# DME_Board_1.net
KiCad netlist of a schematic drawn in EAGLE
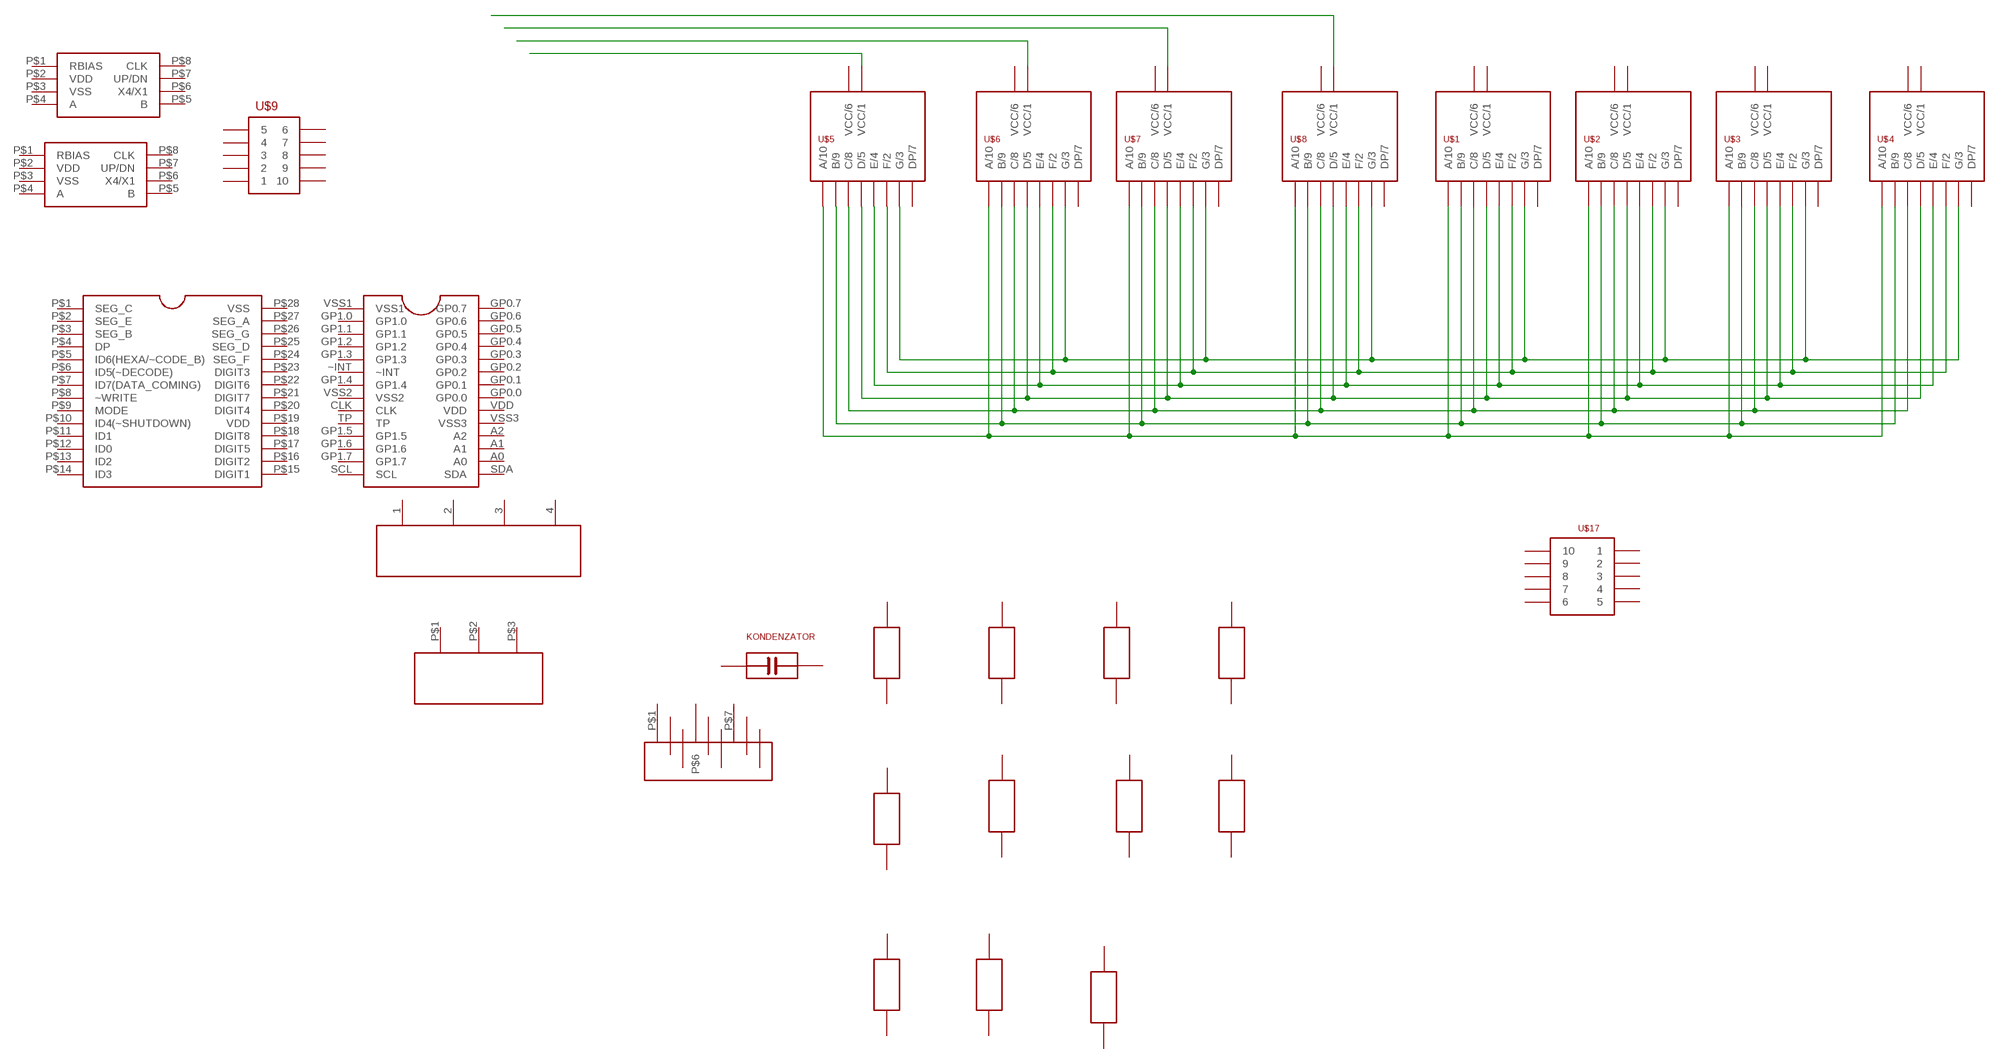
[diagram p0: schematic, sheet 1]

(export (version "E")
  (design (tool "Eeschema 10.0.6"))
  (components
    (comp (ref "U$1")
      (value "SA3611EWA")
      (footprint "eagle-import:SA3611EWA")
      (libsource (lib "eagle-import") (part "SA3611EWA"))
    )
    (comp (ref "U$2")
      (value "SA3611EWA")
      (footprint "eagle-import:SA3611EWA")
      (libsource (lib "eagle-import") (part "SA3611EWA"))
    )
    (comp (ref "U$3")
      (value "SA3611EWA")
      (footprint "eagle-import:SA3611EWA")
      (libsource (lib "eagle-import") (part "SA3611EWA"))
    )
    (comp (ref "U$4")
      (value "SA3611EWA")
      (footprint "eagle-import:SA3611EWA")
      (libsource (lib "eagle-import") (part "SA3611EWA"))
    )
    (comp (ref "U$5")
      (value "SA3611EWA")
      (footprint "eagle-import:SA3611EWA")
      (libsource (lib "eagle-import") (part "SA3611EWA"))
    )
    (comp (ref "U$6")
      (value "SA3611EWA")
      (footprint "eagle-import:SA3611EWA")
      (libsource (lib "eagle-import") (part "SA3611EWA"))
    )
    (comp (ref "U$7")
      (value "SA3611EWA")
      (footprint "eagle-import:SA3611EWA")
      (libsource (lib "eagle-import") (part "SA3611EWA"))
    )
    (comp (ref "U$8")
      (value "SA3611EWA")
      (footprint "eagle-import:SA3611EWA")
      (libsource (lib "eagle-import") (part "SA3611EWA"))
    )
    (comp (ref "U$9")
      (value "ELMA_E37")
      (footprint "eagle-import:ELMA_E37")
      (libsource (lib "eagle-import") (part "ELMA_E37"))
    )
    (comp (ref "U$10")
      (value "46311LD")
      (footprint "eagle-import:46311LD")
      (libsource (lib "eagle-import") (part "46311LD"))
    )
    (comp (ref "U$11")
      (value "REZISTOR")
      (footprint "eagle-import:REZISTOR")
      (libsource (lib "eagle-import") (part "REZISTOR"))
    )
    (comp (ref "U$12")
      (value "T220")
      (footprint "eagle-import:T220")
      (libsource (lib "eagle-import") (part "T220"))
    )
    (comp (ref "U$13")
      (value "REZISTOR")
      (footprint "eagle-import:REZISTOR")
      (libsource (lib "eagle-import") (part "REZISTOR"))
    )
    (comp (ref "U$14")
      (value "ICM7228A")
      (footprint "eagle-import:ICM7228A")
      (libsource (lib "eagle-import") (part "ICM7228A"))
    )
    (comp (ref "U$15")
      (value "REZISTOR")
      (footprint "eagle-import:REZISTOR")
      (libsource (lib "eagle-import") (part "REZISTOR"))
    )
    (comp (ref "U$16")
      (value "MCP23016")
      (footprint "eagle-import:MCP23016")
      (libsource (lib "eagle-import") (part "MCP23016"))
    )
    (comp (ref "U$17")
      (value "LISTA_2X5")
      (footprint "eagle-import:LISTA_2X5")
      (libsource (lib "eagle-import") (part "LISTA_2X5"))
    )
    (comp (ref "U$19")
      (value "REZISTOR")
      (footprint "eagle-import:REZISTOR")
      (libsource (lib "eagle-import") (part "REZISTOR"))
    )
    (comp (ref "U$21")
      (value "LS7084")
      (footprint "eagle-import:LS7084")
      (libsource (lib "eagle-import") (part "LS7084"))
    )
    (comp (ref "U$22")
      (value "LS7084")
      (footprint "eagle-import:LS7084")
      (libsource (lib "eagle-import") (part "LS7084"))
    )
    (comp (ref "U$23")
      (value "KONDENZATOR")
      (footprint "eagle-import:KONDENZATOR")
      (libsource (lib "eagle-import") (part "KONDENZATOR"))
    )
    (comp (ref "U$24")
      (value "ADRESA_0..2")
      (footprint "eagle-import:ADRESA_0..2")
      (libsource (lib "eagle-import") (part "ADRESA_0..2"))
    )
    (comp (ref "U$25")
      (value "REZISTOR")
      (footprint "eagle-import:REZISTOR")
      (libsource (lib "eagle-import") (part "REZISTOR"))
    )
    (comp (ref "U$26")
      (value "REZISTOR")
      (footprint "eagle-import:REZISTOR")
      (libsource (lib "eagle-import") (part "REZISTOR"))
    )
    (comp (ref "U$27")
      (value "REZISTOR")
      (footprint "eagle-import:REZISTOR")
      (libsource (lib "eagle-import") (part "REZISTOR"))
    )
    (comp (ref "U$28")
      (value "REZISTOR")
      (footprint "eagle-import:REZISTOR")
      (libsource (lib "eagle-import") (part "REZISTOR"))
    )
    (comp (ref "U$29")
      (value "REZISTOR")
      (footprint "eagle-import:REZISTOR")
      (libsource (lib "eagle-import") (part "REZISTOR"))
    )
    (comp (ref "U$30")
      (value "REZISTOR")
      (footprint "eagle-import:REZISTOR")
      (libsource (lib "eagle-import") (part "REZISTOR"))
    )
    (comp (ref "U$31")
      (value "REZISTOR")
      (footprint "eagle-import:REZISTOR")
      (libsource (lib "eagle-import") (part "REZISTOR"))
    )
  )
  (nets
    (net (code "1") (name "Net-(U$1-A{slash}10)") (class "Default")
      (node (ref "U$1") (pin "10") (pinfunction "A/10_10") (pintype "bidirectional"))
      (node (ref "U$2") (pin "10") (pinfunction "A/10_10") (pintype "bidirectional"))
      (node (ref "U$3") (pin "10") (pinfunction "A/10_10") (pintype "bidirectional"))
      (node (ref "U$4") (pin "10") (pinfunction "A/10_10") (pintype "bidirectional"))
      (node (ref "U$5") (pin "10") (pinfunction "A/10_10") (pintype "bidirectional"))
      (node (ref "U$6") (pin "10") (pinfunction "A/10_10") (pintype "bidirectional"))
      (node (ref "U$7") (pin "10") (pinfunction "A/10_10") (pintype "bidirectional"))
      (node (ref "U$8") (pin "10") (pinfunction "A/10_10") (pintype "bidirectional"))
    )
    (net (code "2") (name "Net-(U$1-B{slash}9)") (class "Default")
      (node (ref "U$1") (pin "9") (pinfunction "B/9_9") (pintype "bidirectional"))
      (node (ref "U$2") (pin "9") (pinfunction "B/9_9") (pintype "bidirectional"))
      (node (ref "U$3") (pin "9") (pinfunction "B/9_9") (pintype "bidirectional"))
      (node (ref "U$4") (pin "9") (pinfunction "B/9_9") (pintype "bidirectional"))
      (node (ref "U$5") (pin "9") (pinfunction "B/9_9") (pintype "bidirectional"))
      (node (ref "U$6") (pin "9") (pinfunction "B/9_9") (pintype "bidirectional"))
      (node (ref "U$7") (pin "9") (pinfunction "B/9_9") (pintype "bidirectional"))
      (node (ref "U$8") (pin "9") (pinfunction "B/9_9") (pintype "bidirectional"))
    )
    (net (code "3") (name "Net-(U$1-C{slash}8)") (class "Default")
      (node (ref "U$1") (pin "8") (pinfunction "C/8_8") (pintype "bidirectional"))
      (node (ref "U$2") (pin "8") (pinfunction "C/8_8") (pintype "bidirectional"))
      (node (ref "U$3") (pin "8") (pinfunction "C/8_8") (pintype "bidirectional"))
      (node (ref "U$4") (pin "8") (pinfunction "C/8_8") (pintype "bidirectional"))
      (node (ref "U$5") (pin "8") (pinfunction "C/8_8") (pintype "bidirectional"))
      (node (ref "U$6") (pin "8") (pinfunction "C/8_8") (pintype "bidirectional"))
      (node (ref "U$7") (pin "8") (pinfunction "C/8_8") (pintype "bidirectional"))
      (node (ref "U$8") (pin "8") (pinfunction "C/8_8") (pintype "bidirectional"))
    )
    (net (code "4") (name "Net-(U$1-D{slash}5)") (class "Default")
      (node (ref "U$1") (pin "5") (pinfunction "D/5_5") (pintype "bidirectional"))
      (node (ref "U$2") (pin "5") (pinfunction "D/5_5") (pintype "bidirectional"))
      (node (ref "U$3") (pin "5") (pinfunction "D/5_5") (pintype "bidirectional"))
      (node (ref "U$4") (pin "5") (pinfunction "D/5_5") (pintype "bidirectional"))
      (node (ref "U$5") (pin "5") (pinfunction "D/5_5") (pintype "bidirectional"))
      (node (ref "U$6") (pin "5") (pinfunction "D/5_5") (pintype "bidirectional"))
      (node (ref "U$7") (pin "5") (pinfunction "D/5_5") (pintype "bidirectional"))
      (node (ref "U$8") (pin "5") (pinfunction "D/5_5") (pintype "bidirectional"))
    )
    (net (code "5") (name "Net-(U$1-E{slash}4)") (class "Default")
      (node (ref "U$1") (pin "4") (pinfunction "E/4_4") (pintype "bidirectional"))
      (node (ref "U$2") (pin "4") (pinfunction "E/4_4") (pintype "bidirectional"))
      (node (ref "U$3") (pin "4") (pinfunction "E/4_4") (pintype "bidirectional"))
      (node (ref "U$4") (pin "4") (pinfunction "E/4_4") (pintype "bidirectional"))
      (node (ref "U$5") (pin "4") (pinfunction "E/4_4") (pintype "bidirectional"))
      (node (ref "U$6") (pin "4") (pinfunction "E/4_4") (pintype "bidirectional"))
      (node (ref "U$7") (pin "4") (pinfunction "E/4_4") (pintype "bidirectional"))
      (node (ref "U$8") (pin "4") (pinfunction "E/4_4") (pintype "bidirectional"))
    )
    (net (code "6") (name "Net-(U$1-F{slash}2)") (class "Default")
      (node (ref "U$1") (pin "2") (pinfunction "F/2_2") (pintype "bidirectional"))
      (node (ref "U$2") (pin "2") (pinfunction "F/2_2") (pintype "bidirectional"))
      (node (ref "U$3") (pin "2") (pinfunction "F/2_2") (pintype "bidirectional"))
      (node (ref "U$4") (pin "2") (pinfunction "F/2_2") (pintype "bidirectional"))
      (node (ref "U$5") (pin "2") (pinfunction "F/2_2") (pintype "bidirectional"))
      (node (ref "U$6") (pin "2") (pinfunction "F/2_2") (pintype "bidirectional"))
      (node (ref "U$7") (pin "2") (pinfunction "F/2_2") (pintype "bidirectional"))
      (node (ref "U$8") (pin "2") (pinfunction "F/2_2") (pintype "bidirectional"))
    )
    (net (code "7") (name "Net-(U$1-G{slash}3)") (class "Default")
      (node (ref "U$1") (pin "3") (pinfunction "G/3_3") (pintype "bidirectional"))
      (node (ref "U$2") (pin "3") (pinfunction "G/3_3") (pintype "bidirectional"))
      (node (ref "U$3") (pin "3") (pinfunction "G/3_3") (pintype "bidirectional"))
      (node (ref "U$4") (pin "3") (pinfunction "G/3_3") (pintype "bidirectional"))
      (node (ref "U$5") (pin "3") (pinfunction "G/3_3") (pintype "bidirectional"))
      (node (ref "U$6") (pin "3") (pinfunction "G/3_3") (pintype "bidirectional"))
      (node (ref "U$7") (pin "3") (pinfunction "G/3_3") (pintype "bidirectional"))
      (node (ref "U$8") (pin "3") (pinfunction "G/3_3") (pintype "bidirectional"))
    )
    (net (code "8") (name "unconnected-(U$1-DP{slash}7-Pad7)") (class "Default")
      (node (ref "U$1") (pin "7") (pinfunction "DP/7_7") (pintype "bidirectional"))
    )
    (net (code "9") (name "unconnected-(U$1-VCC{slash}1-Pad1)") (class "Default")
      (node (ref "U$1") (pin "1") (pinfunction "VCC/1_1") (pintype "bidirectional"))
    )
    (net (code "10") (name "unconnected-(U$1-VCC{slash}6-Pad6)") (class "Default")
      (node (ref "U$1") (pin "6") (pinfunction "VCC/6_6") (pintype "bidirectional"))
    )
    (net (code "11") (name "unconnected-(U$2-DP{slash}7-Pad7)") (class "Default")
      (node (ref "U$2") (pin "7") (pinfunction "DP/7_7") (pintype "bidirectional"))
    )
    (net (code "12") (name "unconnected-(U$2-VCC{slash}1-Pad1)") (class "Default")
      (node (ref "U$2") (pin "1") (pinfunction "VCC/1_1") (pintype "bidirectional"))
    )
    (net (code "13") (name "unconnected-(U$2-VCC{slash}6-Pad6)") (class "Default")
      (node (ref "U$2") (pin "6") (pinfunction "VCC/6_6") (pintype "bidirectional"))
    )
    (net (code "14") (name "unconnected-(U$3-DP{slash}7-Pad7)") (class "Default")
      (node (ref "U$3") (pin "7") (pinfunction "DP/7_7") (pintype "bidirectional"))
    )
    (net (code "15") (name "unconnected-(U$3-VCC{slash}1-Pad1)") (class "Default")
      (node (ref "U$3") (pin "1") (pinfunction "VCC/1_1") (pintype "bidirectional"))
    )
    (net (code "16") (name "unconnected-(U$3-VCC{slash}6-Pad6)") (class "Default")
      (node (ref "U$3") (pin "6") (pinfunction "VCC/6_6") (pintype "bidirectional"))
    )
    (net (code "17") (name "unconnected-(U$4-DP{slash}7-Pad7)") (class "Default")
      (node (ref "U$4") (pin "7") (pinfunction "DP/7_7") (pintype "bidirectional"))
    )
    (net (code "18") (name "unconnected-(U$4-VCC{slash}1-Pad1)") (class "Default")
      (node (ref "U$4") (pin "1") (pinfunction "VCC/1_1") (pintype "bidirectional"))
    )
    (net (code "19") (name "unconnected-(U$4-VCC{slash}6-Pad6)") (class "Default")
      (node (ref "U$4") (pin "6") (pinfunction "VCC/6_6") (pintype "bidirectional"))
    )
    (net (code "20") (name "unconnected-(U$5-DP{slash}7-Pad7)") (class "Default")
      (node (ref "U$5") (pin "7") (pinfunction "DP/7_7") (pintype "bidirectional"))
    )
    (net (code "21") (name "unconnected-(U$5-VCC{slash}1-Pad1)") (class "Default")
      (node (ref "U$5") (pin "1") (pinfunction "VCC/1_1") (pintype "bidirectional"))
    )
    (net (code "22") (name "unconnected-(U$5-VCC{slash}6-Pad6)") (class "Default")
      (node (ref "U$5") (pin "6") (pinfunction "VCC/6_6") (pintype "bidirectional"))
    )
    (net (code "23") (name "unconnected-(U$6-DP{slash}7-Pad7)") (class "Default")
      (node (ref "U$6") (pin "7") (pinfunction "DP/7_7") (pintype "bidirectional"))
    )
    (net (code "24") (name "unconnected-(U$6-VCC{slash}1-Pad1)") (class "Default")
      (node (ref "U$6") (pin "1") (pinfunction "VCC/1_1") (pintype "bidirectional"))
    )
    (net (code "25") (name "unconnected-(U$6-VCC{slash}6-Pad6)") (class "Default")
      (node (ref "U$6") (pin "6") (pinfunction "VCC/6_6") (pintype "bidirectional"))
    )
    (net (code "26") (name "unconnected-(U$7-DP{slash}7-Pad7)") (class "Default")
      (node (ref "U$7") (pin "7") (pinfunction "DP/7_7") (pintype "bidirectional"))
    )
    (net (code "27") (name "unconnected-(U$7-VCC{slash}1-Pad1)") (class "Default")
      (node (ref "U$7") (pin "1") (pinfunction "VCC/1_1") (pintype "bidirectional"))
    )
    (net (code "28") (name "unconnected-(U$7-VCC{slash}6-Pad6)") (class "Default")
      (node (ref "U$7") (pin "6") (pinfunction "VCC/6_6") (pintype "bidirectional"))
    )
    (net (code "29") (name "unconnected-(U$8-DP{slash}7-Pad7)") (class "Default")
      (node (ref "U$8") (pin "7") (pinfunction "DP/7_7") (pintype "bidirectional"))
    )
    (net (code "30") (name "unconnected-(U$8-VCC{slash}1-Pad1)") (class "Default")
      (node (ref "U$8") (pin "1") (pinfunction "VCC/1_1") (pintype "bidirectional"))
    )
    (net (code "31") (name "unconnected-(U$8-VCC{slash}6-Pad6)") (class "Default")
      (node (ref "U$8") (pin "6") (pinfunction "VCC/6_6") (pintype "bidirectional"))
    )
    (net (code "32") (name "unconnected-(U$9-Pad1)") (class "Default")
      (node (ref "U$9") (pin "1") (pinfunction "1_1") (pintype "bidirectional"))
    )
    (net (code "33") (name "unconnected-(U$9-Pad2)") (class "Default")
      (node (ref "U$9") (pin "2") (pinfunction "2_2") (pintype "bidirectional"))
    )
    (net (code "34") (name "unconnected-(U$9-Pad3)") (class "Default")
      (node (ref "U$9") (pin "3") (pinfunction "3_3") (pintype "bidirectional"))
    )
    (net (code "35") (name "unconnected-(U$9-Pad4)") (class "Default")
      (node (ref "U$9") (pin "4") (pinfunction "4_4") (pintype "bidirectional"))
    )
    (net (code "36") (name "unconnected-(U$9-Pad5)") (class "Default")
      (node (ref "U$9") (pin "5") (pinfunction "5_5") (pintype "bidirectional"))
    )
    (net (code "37") (name "unconnected-(U$9-Pad6)") (class "Default")
      (node (ref "U$9") (pin "6") (pinfunction "6_6") (pintype "bidirectional"))
    )
    (net (code "38") (name "unconnected-(U$9-Pad7)") (class "Default")
      (node (ref "U$9") (pin "7") (pinfunction "7_7") (pintype "bidirectional"))
    )
    (net (code "39") (name "unconnected-(U$9-Pad8)") (class "Default")
      (node (ref "U$9") (pin "8") (pinfunction "8_8") (pintype "bidirectional"))
    )
    (net (code "40") (name "unconnected-(U$9-Pad9)") (class "Default")
      (node (ref "U$9") (pin "9") (pinfunction "9_9") (pintype "bidirectional"))
    )
    (net (code "41") (name "unconnected-(U$9-Pad10)") (class "Default")
      (node (ref "U$9") (pin "10") (pinfunction "10_10") (pintype "bidirectional"))
    )
    (net (code "42") (name "unconnected-(U$10-P$1-Pad1)") (class "Default")
      (node (ref "U$10") (pin "1") (pinfunction "P$1_1") (pintype "bidirectional"))
    )
    (net (code "43") (name "unconnected-(U$10-P$2-Pad2)") (class "Default")
      (node (ref "U$10") (pin "2") (pinfunction "P$2_2") (pintype "bidirectional"))
    )
    (net (code "44") (name "unconnected-(U$10-P$3-Pad3)") (class "Default")
      (node (ref "U$10") (pin "3") (pinfunction "P$3_3") (pintype "bidirectional"))
    )
    (net (code "45") (name "unconnected-(U$10-P$4-Pad4)") (class "Default")
      (node (ref "U$10") (pin "4") (pinfunction "P$4_4") (pintype "bidirectional"))
    )
    (net (code "46") (name "unconnected-(U$11-PadP$1)") (class "Default")
      (node (ref "U$11") (pin "P$1") (pinfunction "P$1_P$1") (pintype "bidirectional"))
    )
    (net (code "47") (name "unconnected-(U$11-PadP$2)") (class "Default")
      (node (ref "U$11") (pin "P$2") (pinfunction "P$2_P$2") (pintype "bidirectional"))
    )
    (net (code "48") (name "unconnected-(U$12-PadP$1)") (class "Default")
      (node (ref "U$12") (pin "P$1") (pinfunction "P$1_P$1") (pintype "bidirectional"))
    )
    (net (code "49") (name "unconnected-(U$12-PadP$2)") (class "Default")
      (node (ref "U$12") (pin "P$2") (pinfunction "P$2_P$2") (pintype "bidirectional"))
    )
    (net (code "50") (name "unconnected-(U$12-PadP$3)") (class "Default")
      (node (ref "U$12") (pin "P$3") (pinfunction "P$3_P$3") (pintype "bidirectional"))
    )
    (net (code "51") (name "unconnected-(U$13-PadP$1)") (class "Default")
      (node (ref "U$13") (pin "P$1") (pinfunction "P$1_P$1") (pintype "bidirectional"))
    )
    (net (code "52") (name "unconnected-(U$13-PadP$2)") (class "Default")
      (node (ref "U$13") (pin "P$2") (pinfunction "P$2_P$2") (pintype "bidirectional"))
    )
    (net (code "53") (name "unconnected-(U$14-DIGIT1-PadP$15)") (class "Default")
      (node (ref "U$14") (pin "P$15") (pinfunction "DIGIT1_P$15") (pintype "bidirectional"))
    )
    (net (code "54") (name "unconnected-(U$14-DIGIT2-PadP$16)") (class "Default")
      (node (ref "U$14") (pin "P$16") (pinfunction "DIGIT2_P$16") (pintype "bidirectional"))
    )
    (net (code "55") (name "unconnected-(U$14-DIGIT3-PadP$23)") (class "Default")
      (node (ref "U$14") (pin "P$23") (pinfunction "DIGIT3_P$23") (pintype "bidirectional"))
    )
    (net (code "56") (name "unconnected-(U$14-DIGIT4-PadP$20)") (class "Default")
      (node (ref "U$14") (pin "P$20") (pinfunction "DIGIT4_P$20") (pintype "bidirectional"))
    )
    (net (code "57") (name "unconnected-(U$14-DIGIT5-PadP$17)") (class "Default")
      (node (ref "U$14") (pin "P$17") (pinfunction "DIGIT5_P$17") (pintype "bidirectional"))
    )
    (net (code "58") (name "unconnected-(U$14-DIGIT6-PadP$22)") (class "Default")
      (node (ref "U$14") (pin "P$22") (pinfunction "DIGIT6_P$22") (pintype "bidirectional"))
    )
    (net (code "59") (name "unconnected-(U$14-DIGIT7-PadP$21)") (class "Default")
      (node (ref "U$14") (pin "P$21") (pinfunction "DIGIT7_P$21") (pintype "bidirectional"))
    )
    (net (code "60") (name "unconnected-(U$14-DIGIT8-PadP$18)") (class "Default")
      (node (ref "U$14") (pin "P$18") (pinfunction "DIGIT8_P$18") (pintype "bidirectional"))
    )
    (net (code "61") (name "unconnected-(U$14-DP-PadP$4)") (class "Default")
      (node (ref "U$14") (pin "P$4") (pinfunction "DP_P$4") (pintype "bidirectional"))
    )
    (net (code "62") (name "unconnected-(U$14-ID0-PadP$12)") (class "Default")
      (node (ref "U$14") (pin "P$12") (pinfunction "ID0_P$12") (pintype "bidirectional"))
    )
    (net (code "63") (name "unconnected-(U$14-ID1-PadP$11)") (class "Default")
      (node (ref "U$14") (pin "P$11") (pinfunction "ID1_P$11") (pintype "bidirectional"))
    )
    (net (code "64") (name "unconnected-(U$14-ID2-PadP$13)") (class "Default")
      (node (ref "U$14") (pin "P$13") (pinfunction "ID2_P$13") (pintype "bidirectional"))
    )
    (net (code "65") (name "unconnected-(U$14-ID3-PadP$14)") (class "Default")
      (node (ref "U$14") (pin "P$14") (pinfunction "ID3_P$14") (pintype "bidirectional"))
    )
    (net (code "66") (name "unconnected-(U$14-ID4(~{SHUTDOWN})-PadP$10)") (class "Default")
      (node (ref "U$14") (pin "P$10") (pinfunction "ID4(~{SHUTDOWN})_P$10") (pintype "bidirectional"))
    )
    (net (code "67") (name "unconnected-(U$14-ID5(~{DECODE})-PadP$6)") (class "Default")
      (node (ref "U$14") (pin "P$6") (pinfunction "ID5(~{DECODE})_P$6") (pintype "bidirectional"))
    )
    (net (code "68") (name "unconnected-(U$14-ID6(HEXA{slash}~{CODE_B})-PadP$5)") (class "Default")
      (node (ref "U$14") (pin "P$5") (pinfunction "ID6(HEXA/~{CODE_B})_P$5") (pintype "bidirectional"))
    )
    (net (code "69") (name "unconnected-(U$14-ID7(DATA_COMING)-PadP$7)") (class "Default")
      (node (ref "U$14") (pin "P$7") (pinfunction "ID7(DATA_COMING)_P$7") (pintype "bidirectional"))
    )
    (net (code "70") (name "unconnected-(U$14-MODE-PadP$9)") (class "Default")
      (node (ref "U$14") (pin "P$9") (pinfunction "MODE_P$9") (pintype "bidirectional"))
    )
    (net (code "71") (name "unconnected-(U$14-SEG_A-PadP$27)") (class "Default")
      (node (ref "U$14") (pin "P$27") (pinfunction "SEG_A_P$27") (pintype "bidirectional"))
    )
    (net (code "72") (name "unconnected-(U$14-SEG_B-PadP$3)") (class "Default")
      (node (ref "U$14") (pin "P$3") (pinfunction "SEG_B_P$3") (pintype "bidirectional"))
    )
    (net (code "73") (name "unconnected-(U$14-SEG_C-PadP$1)") (class "Default")
      (node (ref "U$14") (pin "P$1") (pinfunction "SEG_C_P$1") (pintype "bidirectional"))
    )
    (net (code "74") (name "unconnected-(U$14-SEG_D-PadP$25)") (class "Default")
      (node (ref "U$14") (pin "P$25") (pinfunction "SEG_D_P$25") (pintype "bidirectional"))
    )
    (net (code "75") (name "unconnected-(U$14-SEG_E-PadP$2)") (class "Default")
      (node (ref "U$14") (pin "P$2") (pinfunction "SEG_E_P$2") (pintype "bidirectional"))
    )
    (net (code "76") (name "unconnected-(U$14-SEG_F-PadP$24)") (class "Default")
      (node (ref "U$14") (pin "P$24") (pinfunction "SEG_F_P$24") (pintype "bidirectional"))
    )
    (net (code "77") (name "unconnected-(U$14-SEG_G-PadP$26)") (class "Default")
      (node (ref "U$14") (pin "P$26") (pinfunction "SEG_G_P$26") (pintype "bidirectional"))
    )
    (net (code "78") (name "unconnected-(U$14-VDD-PadP$19)") (class "Default")
      (node (ref "U$14") (pin "P$19") (pinfunction "VDD_P$19") (pintype "bidirectional"))
    )
    (net (code "79") (name "unconnected-(U$14-VSS-PadP$28)") (class "Default")
      (node (ref "U$14") (pin "P$28") (pinfunction "VSS_P$28") (pintype "bidirectional"))
    )
    (net (code "80") (name "unconnected-(U$14-~{WRITE}-PadP$8)") (class "Default")
      (node (ref "U$14") (pin "P$8") (pinfunction "~{WRITE}_P$8") (pintype "bidirectional"))
    )
    (net (code "81") (name "unconnected-(U$15-PadP$1)") (class "Default")
      (node (ref "U$15") (pin "P$1") (pinfunction "P$1_P$1") (pintype "bidirectional"))
    )
    (net (code "82") (name "unconnected-(U$15-PadP$2)") (class "Default")
      (node (ref "U$15") (pin "P$2") (pinfunction "P$2_P$2") (pintype "bidirectional"))
    )
    (net (code "83") (name "unconnected-(U$16-PadA0)") (class "Default")
      (node (ref "U$16") (pin "A0") (pinfunction "A0_A0") (pintype "bidirectional"))
    )
    (net (code "84") (name "unconnected-(U$16-PadA1)") (class "Default")
      (node (ref "U$16") (pin "A1") (pinfunction "A1_A1") (pintype "bidirectional"))
    )
    (net (code "85") (name "unconnected-(U$16-PadA2)") (class "Default")
      (node (ref "U$16") (pin "A2") (pinfunction "A2_A2") (pintype "bidirectional"))
    )
    (net (code "86") (name "unconnected-(U$16-PadCLK)") (class "Default")
      (node (ref "U$16") (pin "CLK") (pinfunction "CLK_CLK") (pintype "bidirectional"))
    )
    (net (code "87") (name "unconnected-(U$16-PadGP0.0)") (class "Default")
      (node (ref "U$16") (pin "GP0.0") (pinfunction "GP0.0_GP0.0") (pintype "bidirectional"))
    )
    (net (code "88") (name "unconnected-(U$16-PadGP0.1)") (class "Default")
      (node (ref "U$16") (pin "GP0.1") (pinfunction "GP0.1_GP0.1") (pintype "bidirectional"))
    )
    (net (code "89") (name "unconnected-(U$16-PadGP0.2)") (class "Default")
      (node (ref "U$16") (pin "GP0.2") (pinfunction "GP0.2_GP0.2") (pintype "bidirectional"))
    )
    (net (code "90") (name "unconnected-(U$16-PadGP0.3)") (class "Default")
      (node (ref "U$16") (pin "GP0.3") (pinfunction "GP0.3_GP0.3") (pintype "bidirectional"))
    )
    (net (code "91") (name "unconnected-(U$16-PadGP0.4)") (class "Default")
      (node (ref "U$16") (pin "GP0.4") (pinfunction "GP0.4_GP0.4") (pintype "bidirectional"))
    )
    (net (code "92") (name "unconnected-(U$16-PadGP0.5)") (class "Default")
      (node (ref "U$16") (pin "GP0.5") (pinfunction "GP0.5_GP0.5") (pintype "bidirectional"))
    )
    (net (code "93") (name "unconnected-(U$16-PadGP0.6)") (class "Default")
      (node (ref "U$16") (pin "GP0.6") (pinfunction "GP0.6_GP0.6") (pintype "bidirectional"))
    )
    (net (code "94") (name "unconnected-(U$16-PadGP0.7)") (class "Default")
      (node (ref "U$16") (pin "GP0.7") (pinfunction "GP0.7_GP0.7") (pintype "bidirectional"))
    )
    (net (code "95") (name "unconnected-(U$16-PadGP1.0)") (class "Default")
      (node (ref "U$16") (pin "GP1.0") (pinfunction "GP1.0_GP1.0") (pintype "bidirectional"))
    )
    (net (code "96") (name "unconnected-(U$16-PadGP1.1)") (class "Default")
      (node (ref "U$16") (pin "GP1.1") (pinfunction "GP1.1_GP1.1") (pintype "bidirectional"))
    )
    (net (code "97") (name "unconnected-(U$16-PadGP1.2)") (class "Default")
      (node (ref "U$16") (pin "GP1.2") (pinfunction "GP1.2_GP1.2") (pintype "bidirectional"))
    )
    (net (code "98") (name "unconnected-(U$16-PadGP1.3)") (class "Default")
      (node (ref "U$16") (pin "GP1.3") (pinfunction "GP1.3_GP1.3") (pintype "bidirectional"))
    )
    (net (code "99") (name "unconnected-(U$16-PadGP1.4)") (class "Default")
      (node (ref "U$16") (pin "GP1.4") (pinfunction "GP1.4_GP1.4") (pintype "bidirectional"))
    )
    (net (code "100") (name "unconnected-(U$16-PadGP1.5)") (class "Default")
      (node (ref "U$16") (pin "GP1.5") (pinfunction "GP1.5_GP1.5") (pintype "bidirectional"))
    )
    (net (code "101") (name "unconnected-(U$16-PadGP1.6)") (class "Default")
      (node (ref "U$16") (pin "GP1.6") (pinfunction "GP1.6_GP1.6") (pintype "bidirectional"))
    )
    (net (code "102") (name "unconnected-(U$16-PadGP1.7)") (class "Default")
      (node (ref "U$16") (pin "GP1.7") (pinfunction "GP1.7_GP1.7") (pintype "bidirectional"))
    )
    (net (code "103") (name "unconnected-(U$16-PadSCL)") (class "Default")
      (node (ref "U$16") (pin "SCL") (pinfunction "SCL_SCL") (pintype "bidirectional"))
    )
    (net (code "104") (name "unconnected-(U$16-PadSDA)") (class "Default")
      (node (ref "U$16") (pin "SDA") (pinfunction "SDA_SDA") (pintype "bidirectional"))
    )
    (net (code "105") (name "unconnected-(U$16-PadTP)") (class "Default")
      (node (ref "U$16") (pin "TP") (pinfunction "TP_TP") (pintype "bidirectional"))
    )
    (net (code "106") (name "unconnected-(U$16-PadVDD)") (class "Default")
      (node (ref "U$16") (pin "VDD") (pinfunction "VDD_VDD") (pintype "bidirectional"))
    )
    (net (code "107") (name "unconnected-(U$16-PadVSS1)") (class "Default")
      (node (ref "U$16") (pin "VSS1") (pinfunction "VSS1_VSS1") (pintype "bidirectional"))
    )
    (net (code "108") (name "unconnected-(U$16-PadVSS2)") (class "Default")
      (node (ref "U$16") (pin "VSS2") (pinfunction "VSS2_VSS2") (pintype "bidirectional"))
    )
    (net (code "109") (name "unconnected-(U$16-PadVSS3)") (class "Default")
      (node (ref "U$16") (pin "VSS3") (pinfunction "VSS3_VSS3") (pintype "bidirectional"))
    )
    (net (code "110") (name "unconnected-(U$16-~{INT}-Pad~INT)") (class "Default")
      (node (ref "U$16") (pin "~INT") (pinfunction "~{INT}_~INT") (pintype "bidirectional"))
    )
    (net (code "111") (name "unconnected-(U$17-Pad1)") (class "Default")
      (node (ref "U$17") (pin "1") (pinfunction "1_1") (pintype "bidirectional"))
    )
    (net (code "112") (name "unconnected-(U$17-Pad2)") (class "Default")
      (node (ref "U$17") (pin "2") (pinfunction "2_2") (pintype "bidirectional"))
    )
    (net (code "113") (name "unconnected-(U$17-Pad3)") (class "Default")
      (node (ref "U$17") (pin "3") (pinfunction "3_3") (pintype "bidirectional"))
    )
    (net (code "114") (name "unconnected-(U$17-Pad4)") (class "Default")
      (node (ref "U$17") (pin "4") (pinfunction "4_4") (pintype "bidirectional"))
    )
    (net (code "115") (name "unconnected-(U$17-Pad5)") (class "Default")
      (node (ref "U$17") (pin "5") (pinfunction "5_5") (pintype "bidirectional"))
    )
    (net (code "116") (name "unconnected-(U$17-Pad6)") (class "Default")
      (node (ref "U$17") (pin "6") (pinfunction "6_6") (pintype "bidirectional"))
    )
    (net (code "117") (name "unconnected-(U$17-Pad7)") (class "Default")
      (node (ref "U$17") (pin "7") (pinfunction "7_7") (pintype "bidirectional"))
    )
    (net (code "118") (name "unconnected-(U$17-Pad8)") (class "Default")
      (node (ref "U$17") (pin "8") (pinfunction "8_8") (pintype "bidirectional"))
    )
    (net (code "119") (name "unconnected-(U$17-Pad9)") (class "Default")
      (node (ref "U$17") (pin "9") (pinfunction "9_9") (pintype "bidirectional"))
    )
    (net (code "120") (name "unconnected-(U$17-Pad10)") (class "Default")
      (node (ref "U$17") (pin "10") (pinfunction "10_10") (pintype "bidirectional"))
    )
    (net (code "121") (name "unconnected-(U$19-PadP$1)") (class "Default")
      (node (ref "U$19") (pin "P$1") (pinfunction "P$1_P$1") (pintype "bidirectional"))
    )
    (net (code "122") (name "unconnected-(U$19-PadP$2)") (class "Default")
      (node (ref "U$19") (pin "P$2") (pinfunction "P$2_P$2") (pintype "bidirectional"))
    )
    (net (code "123") (name "unconnected-(U$21-A-PadP$4)") (class "Default")
      (node (ref "U$21") (pin "P$4") (pinfunction "A_P$4") (pintype "bidirectional"))
    )
    (net (code "124") (name "unconnected-(U$21-B-PadP$5)") (class "Default")
      (node (ref "U$21") (pin "P$5") (pinfunction "B_P$5") (pintype "bidirectional"))
    )
    (net (code "125") (name "unconnected-(U$21-CLK-PadP$8)") (class "Default")
      (node (ref "U$21") (pin "P$8") (pinfunction "CLK_P$8") (pintype "bidirectional"))
    )
    (net (code "126") (name "unconnected-(U$21-RBIAS-PadP$1)") (class "Default")
      (node (ref "U$21") (pin "P$1") (pinfunction "RBIAS_P$1") (pintype "bidirectional"))
    )
    (net (code "127") (name "unconnected-(U$21-UP{slash}DN-PadP$7)") (class "Default")
      (node (ref "U$21") (pin "P$7") (pinfunction "UP/DN_P$7") (pintype "bidirectional"))
    )
    (net (code "128") (name "unconnected-(U$21-VDD-PadP$2)") (class "Default")
      (node (ref "U$21") (pin "P$2") (pinfunction "VDD_P$2") (pintype "bidirectional"))
    )
    (net (code "129") (name "unconnected-(U$21-VSS-PadP$3)") (class "Default")
      (node (ref "U$21") (pin "P$3") (pinfunction "VSS_P$3") (pintype "bidirectional"))
    )
    (net (code "130") (name "unconnected-(U$21-X4{slash}X1-PadP$6)") (class "Default")
      (node (ref "U$21") (pin "P$6") (pinfunction "X4/X1_P$6") (pintype "bidirectional"))
    )
    (net (code "131") (name "unconnected-(U$22-A-PadP$4)") (class "Default")
      (node (ref "U$22") (pin "P$4") (pinfunction "A_P$4") (pintype "bidirectional"))
    )
    (net (code "132") (name "unconnected-(U$22-B-PadP$5)") (class "Default")
      (node (ref "U$22") (pin "P$5") (pinfunction "B_P$5") (pintype "bidirectional"))
    )
    (net (code "133") (name "unconnected-(U$22-CLK-PadP$8)") (class "Default")
      (node (ref "U$22") (pin "P$8") (pinfunction "CLK_P$8") (pintype "bidirectional"))
    )
    (net (code "134") (name "unconnected-(U$22-RBIAS-PadP$1)") (class "Default")
      (node (ref "U$22") (pin "P$1") (pinfunction "RBIAS_P$1") (pintype "bidirectional"))
    )
    (net (code "135") (name "unconnected-(U$22-UP{slash}DN-PadP$7)") (class "Default")
      (node (ref "U$22") (pin "P$7") (pinfunction "UP/DN_P$7") (pintype "bidirectional"))
    )
    (net (code "136") (name "unconnected-(U$22-VDD-PadP$2)") (class "Default")
      (node (ref "U$22") (pin "P$2") (pinfunction "VDD_P$2") (pintype "bidirectional"))
    )
    (net (code "137") (name "unconnected-(U$22-VSS-PadP$3)") (class "Default")
      (node (ref "U$22") (pin "P$3") (pinfunction "VSS_P$3") (pintype "bidirectional"))
    )
    (net (code "138") (name "unconnected-(U$22-X4{slash}X1-PadP$6)") (class "Default")
      (node (ref "U$22") (pin "P$6") (pinfunction "X4/X1_P$6") (pintype "bidirectional"))
    )
    (net (code "139") (name "unconnected-(U$23-PadP$1)") (class "Default")
      (node (ref "U$23") (pin "P$1") (pinfunction "P$1_P$1") (pintype "bidirectional"))
    )
    (net (code "140") (name "unconnected-(U$23-PadP$2)") (class "Default")
      (node (ref "U$23") (pin "P$2") (pinfunction "P$2_P$2") (pintype "bidirectional"))
    )
    (net (code "141") (name "unconnected-(U$24-PadP$1)") (class "Default")
      (node (ref "U$24") (pin "P$1") (pinfunction "P$1_P$1") (pintype "bidirectional"))
    )
    (net (code "142") (name "unconnected-(U$24-PadP$2)") (class "Default")
      (node (ref "U$24") (pin "P$2") (pinfunction "P$2_P$2") (pintype "bidirectional"))
    )
    (net (code "143") (name "unconnected-(U$24-PadP$3)") (class "Default")
      (node (ref "U$24") (pin "P$3") (pinfunction "P$3_P$3") (pintype "bidirectional"))
    )
    (net (code "144") (name "unconnected-(U$24-PadP$4)") (class "Default")
      (node (ref "U$24") (pin "P$4") (pinfunction "P$4_P$4") (pintype "bidirectional"))
    )
    (net (code "145") (name "unconnected-(U$24-PadP$5)") (class "Default")
      (node (ref "U$24") (pin "P$5") (pinfunction "P$5_P$5") (pintype "bidirectional"))
    )
    (net (code "146") (name "unconnected-(U$24-PadP$6)") (class "Default")
      (node (ref "U$24") (pin "P$6") (pinfunction "P$6_P$6") (pintype "bidirectional"))
    )
    (net (code "147") (name "unconnected-(U$24-PadP$7)") (class "Default")
      (node (ref "U$24") (pin "P$7") (pinfunction "P$7_P$7") (pintype "bidirectional"))
    )
    (net (code "148") (name "unconnected-(U$24-PadP$8)") (class "Default")
      (node (ref "U$24") (pin "P$8") (pinfunction "P$8_P$8") (pintype "bidirectional"))
    )
    (net (code "149") (name "unconnected-(U$24-PadP$9)") (class "Default")
      (node (ref "U$24") (pin "P$9") (pinfunction "P$9_P$9") (pintype "bidirectional"))
    )
    (net (code "150") (name "unconnected-(U$25-PadP$1)") (class "Default")
      (node (ref "U$25") (pin "P$1") (pinfunction "P$1_P$1") (pintype "bidirectional"))
    )
    (net (code "151") (name "unconnected-(U$25-PadP$2)") (class "Default")
      (node (ref "U$25") (pin "P$2") (pinfunction "P$2_P$2") (pintype "bidirectional"))
    )
    (net (code "152") (name "unconnected-(U$26-PadP$1)") (class "Default")
      (node (ref "U$26") (pin "P$1") (pinfunction "P$1_P$1") (pintype "bidirectional"))
    )
    (net (code "153") (name "unconnected-(U$26-PadP$2)") (class "Default")
      (node (ref "U$26") (pin "P$2") (pinfunction "P$2_P$2") (pintype "bidirectional"))
    )
    (net (code "154") (name "unconnected-(U$27-PadP$1)") (class "Default")
      (node (ref "U$27") (pin "P$1") (pinfunction "P$1_P$1") (pintype "bidirectional"))
    )
    (net (code "155") (name "unconnected-(U$27-PadP$2)") (class "Default")
      (node (ref "U$27") (pin "P$2") (pinfunction "P$2_P$2") (pintype "bidirectional"))
    )
    (net (code "156") (name "unconnected-(U$28-PadP$1)") (class "Default")
      (node (ref "U$28") (pin "P$1") (pinfunction "P$1_P$1") (pintype "bidirectional"))
    )
    (net (code "157") (name "unconnected-(U$28-PadP$2)") (class "Default")
      (node (ref "U$28") (pin "P$2") (pinfunction "P$2_P$2") (pintype "bidirectional"))
    )
    (net (code "158") (name "unconnected-(U$29-PadP$1)") (class "Default")
      (node (ref "U$29") (pin "P$1") (pinfunction "P$1_P$1") (pintype "bidirectional"))
    )
    (net (code "159") (name "unconnected-(U$29-PadP$2)") (class "Default")
      (node (ref "U$29") (pin "P$2") (pinfunction "P$2_P$2") (pintype "bidirectional"))
    )
    (net (code "160") (name "unconnected-(U$30-PadP$1)") (class "Default")
      (node (ref "U$30") (pin "P$1") (pinfunction "P$1_P$1") (pintype "bidirectional"))
    )
    (net (code "161") (name "unconnected-(U$30-PadP$2)") (class "Default")
      (node (ref "U$30") (pin "P$2") (pinfunction "P$2_P$2") (pintype "bidirectional"))
    )
    (net (code "162") (name "unconnected-(U$31-PadP$1)") (class "Default")
      (node (ref "U$31") (pin "P$1") (pinfunction "P$1_P$1") (pintype "bidirectional"))
    )
    (net (code "163") (name "unconnected-(U$31-PadP$2)") (class "Default")
      (node (ref "U$31") (pin "P$2") (pinfunction "P$2_P$2") (pintype "bidirectional"))
    )
  )
)
